# untitled.net
KiCad netlist of a schematic drawn in EAGLE
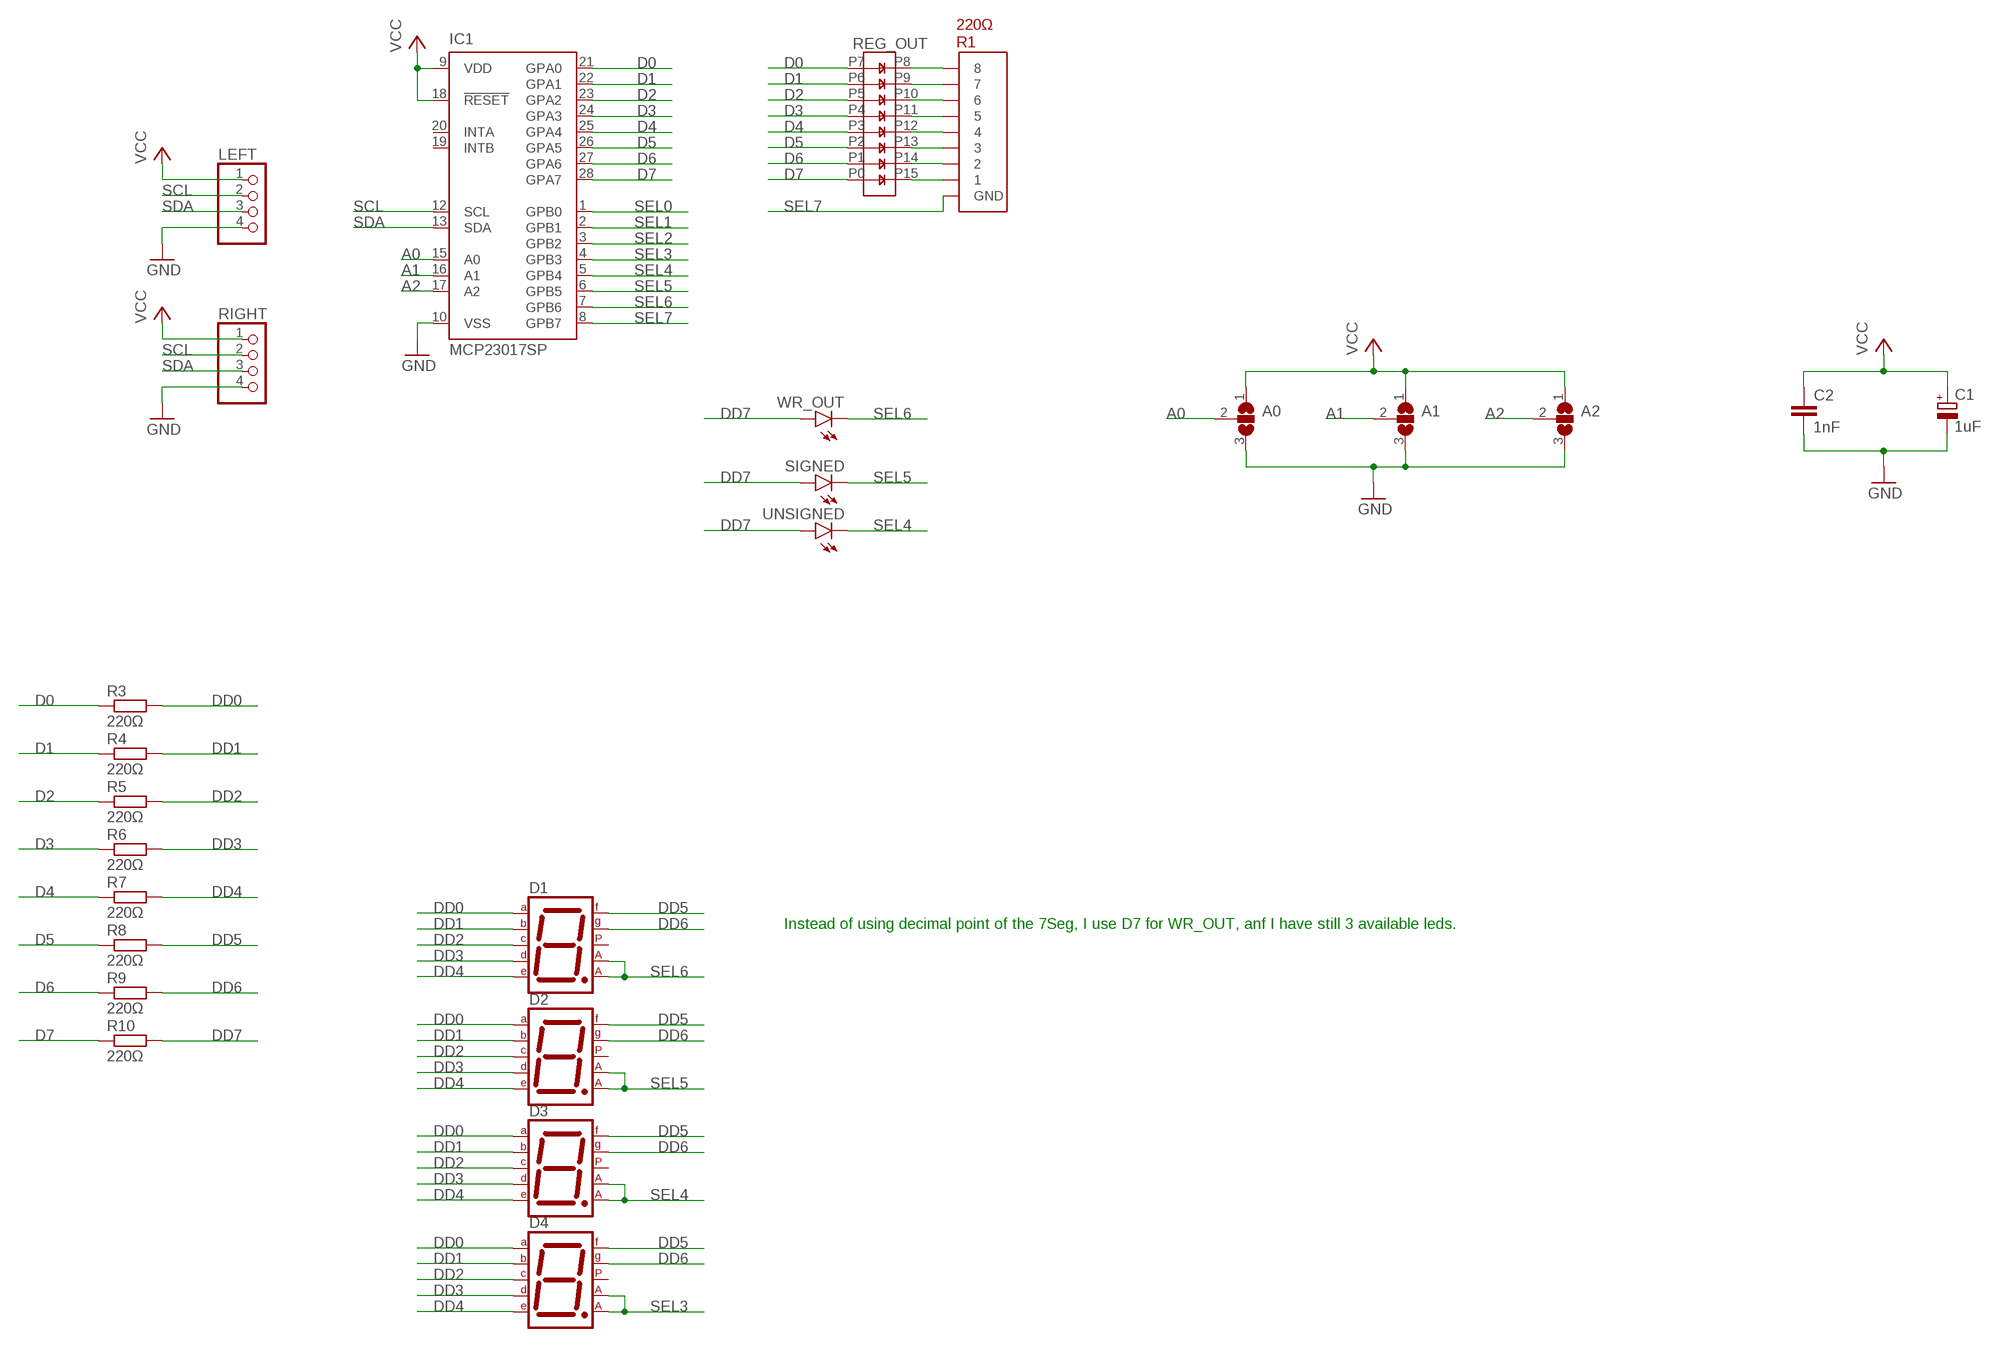
[diagram p0: schematic, sheet 1]

(export (version "E")
  (design (tool "Eeschema 10.0.6"))
  (components
    (comp (ref "A0")
      (value "SJ2W")
      (footprint "eagle-import:SJ_2")
      (libsource (lib "eagle-import") (part "SJ2W"))
    )
    (comp (ref "A1")
      (value "SJ2W")
      (footprint "eagle-import:SJ_2")
      (libsource (lib "eagle-import") (part "SJ2W"))
    )
    (comp (ref "A2")
      (value "SJ2W")
      (footprint "eagle-import:SJ_2")
      (libsource (lib "eagle-import") (part "SJ2W"))
    )
    (comp (ref "C1")
      (value "1uF")
      (footprint "eagle-import:E2,5-6")
      (libsource (lib "eagle-import") (part "CPOL-EUE2.5-6"))
    )
    (comp (ref "C2")
      (value "1nF")
      (footprint "eagle-import:C2.5-2")
      (libsource (lib "eagle-import") (part "C2.5/2"))
    )
    (comp (ref "D1")
      (value "7SEG-CA")
      (footprint "eagle-import:7SEG-13")
      (libsource (lib "eagle-import") (part "7SEG-CA"))
    )
    (comp (ref "D2")
      (value "7SEG-CA")
      (footprint "eagle-import:7SEG-13")
      (libsource (lib "eagle-import") (part "7SEG-CA"))
    )
    (comp (ref "D3")
      (value "7SEG-CA")
      (footprint "eagle-import:7SEG-13")
      (libsource (lib "eagle-import") (part "7SEG-CA"))
    )
    (comp (ref "D4")
      (value "7SEG-CA")
      (footprint "eagle-import:7SEG-13")
      (libsource (lib "eagle-import") (part "7SEG-CA"))
    )
    (comp (ref "IC1")
      (value "MCP23017SP")
      (footprint "eagle-import:DIL28-3")
      (fields (field (name "MF") "MICROCHIP") (field (name "MPN") "MCP23017-E/SP"))
      (libsource (lib "eagle-import") (part "MCP23017SP"))
    )
    (comp (ref "LEFT")
      (value "PINHD-1X4")
      (footprint "eagle-import:1X04")
      (libsource (lib "eagle-import") (part "PINHD-1X4"))
    )
    (comp (ref "R1")
      (value "220Ω")
      (footprint "eagle-import:R_ARRAY_8PIN")
      (libsource (lib "eagle-import") (part "R_ARRAY_8PIN"))
    )
    (comp (ref "R3")
      (value "220Ω")
      (footprint "eagle-import:0207_10")
      (libsource (lib "eagle-import") (part "R-EU_0207/10"))
    )
    (comp (ref "R4")
      (value "220Ω")
      (footprint "eagle-import:0207_10")
      (libsource (lib "eagle-import") (part "R-EU_0207/10"))
    )
    (comp (ref "R5")
      (value "220Ω")
      (footprint "eagle-import:0207_10")
      (libsource (lib "eagle-import") (part "R-EU_0207/10"))
    )
    (comp (ref "R6")
      (value "220Ω")
      (footprint "eagle-import:0207_10")
      (libsource (lib "eagle-import") (part "R-EU_0207/10"))
    )
    (comp (ref "R7")
      (value "220Ω")
      (footprint "eagle-import:0207_10")
      (libsource (lib "eagle-import") (part "R-EU_0207/10"))
    )
    (comp (ref "R8")
      (value "220Ω")
      (footprint "eagle-import:0207_10")
      (libsource (lib "eagle-import") (part "R-EU_0207/10"))
    )
    (comp (ref "R9")
      (value "220Ω")
      (footprint "eagle-import:0207_10")
      (libsource (lib "eagle-import") (part "R-EU_0207/10"))
    )
    (comp (ref "R10")
      (value "220Ω")
      (footprint "eagle-import:0207_10")
      (libsource (lib "eagle-import") (part "R-EU_0207/10"))
    )
    (comp (ref "REG_OUT")
      (value "LB8")
      (footprint "eagle-import:LB8")
      (libsource (lib "eagle-import") (part "LB8"))
    )
    (comp (ref "RIGHT")
      (value "PINHD-1X4")
      (footprint "eagle-import:1X04")
      (libsource (lib "eagle-import") (part "PINHD-1X4"))
    )
    (comp (ref "SIGNED")
      (value "LED3MM")
      (footprint "eagle-import:LED3MM")
      (libsource (lib "eagle-import") (part "LED3MM"))
    )
    (comp (ref "UNSIGNED")
      (value "LED3MM")
      (footprint "eagle-import:LED3MM")
      (libsource (lib "eagle-import") (part "LED3MM"))
    )
    (comp (ref "WR_OUT")
      (value "LED3MM")
      (footprint "eagle-import:LED3MM")
      (libsource (lib "eagle-import") (part "LED3MM"))
    )
  )
  (nets
    (net (code "1") (name "/A0") (class "Default")
      (node (ref "A0") (pin "2") (pinfunction "2_2") (pintype "passive"))
      (node (ref "IC1") (pin "15") (pinfunction "A0_15") (pintype "input"))
    )
    (net (code "2") (name "/A1") (class "Default")
      (node (ref "A1") (pin "2") (pinfunction "2_2") (pintype "passive"))
      (node (ref "IC1") (pin "16") (pinfunction "A1_16") (pintype "input"))
    )
    (net (code "3") (name "/A2") (class "Default")
      (node (ref "A2") (pin "2") (pinfunction "2_2") (pintype "passive"))
      (node (ref "IC1") (pin "17") (pinfunction "A2_17") (pintype "input"))
    )
    (net (code "4") (name "/D0") (class "Default")
      (node (ref "IC1") (pin "21") (pinfunction "GPA0_21") (pintype "bidirectional"))
      (node (ref "R3") (pin "1") (pinfunction "1_1") (pintype "passive"))
      (node (ref "REG_OUT") (pin "P7") (pinfunction "P7_P7") (pintype "bidirectional"))
    )
    (net (code "5") (name "/D1") (class "Default")
      (node (ref "IC1") (pin "22") (pinfunction "GPA1_22") (pintype "bidirectional"))
      (node (ref "R4") (pin "1") (pinfunction "1_1") (pintype "passive"))
      (node (ref "REG_OUT") (pin "P6") (pinfunction "P6_P6") (pintype "bidirectional"))
    )
    (net (code "6") (name "/D2") (class "Default")
      (node (ref "IC1") (pin "23") (pinfunction "GPA2_23") (pintype "bidirectional"))
      (node (ref "R5") (pin "1") (pinfunction "1_1") (pintype "passive"))
      (node (ref "REG_OUT") (pin "P5") (pinfunction "P5_P5") (pintype "bidirectional"))
    )
    (net (code "7") (name "/D3") (class "Default")
      (node (ref "IC1") (pin "24") (pinfunction "GPA3_24") (pintype "bidirectional"))
      (node (ref "R6") (pin "1") (pinfunction "1_1") (pintype "passive"))
      (node (ref "REG_OUT") (pin "P4") (pinfunction "P4_P4") (pintype "bidirectional"))
    )
    (net (code "8") (name "/D4") (class "Default")
      (node (ref "IC1") (pin "25") (pinfunction "GPA4_25") (pintype "bidirectional"))
      (node (ref "R7") (pin "1") (pinfunction "1_1") (pintype "passive"))
      (node (ref "REG_OUT") (pin "P3") (pinfunction "P3_P3") (pintype "bidirectional"))
    )
    (net (code "9") (name "/D5") (class "Default")
      (node (ref "IC1") (pin "26") (pinfunction "GPA5_26") (pintype "bidirectional"))
      (node (ref "R8") (pin "1") (pinfunction "1_1") (pintype "passive"))
      (node (ref "REG_OUT") (pin "P2") (pinfunction "P2_P2") (pintype "bidirectional"))
    )
    (net (code "10") (name "/D6") (class "Default")
      (node (ref "IC1") (pin "27") (pinfunction "GPA6_27") (pintype "bidirectional"))
      (node (ref "R9") (pin "1") (pinfunction "1_1") (pintype "passive"))
      (node (ref "REG_OUT") (pin "P1") (pinfunction "P1_P1") (pintype "bidirectional"))
    )
    (net (code "11") (name "/D7") (class "Default")
      (node (ref "IC1") (pin "28") (pinfunction "GPA7_28") (pintype "bidirectional"))
      (node (ref "R10") (pin "1") (pinfunction "1_1") (pintype "passive"))
      (node (ref "REG_OUT") (pin "P0") (pinfunction "P0_P0") (pintype "bidirectional"))
    )
    (net (code "12") (name "/DD0") (class "Default")
      (node (ref "D1") (pin "7") (pinfunction "A_7") (pintype "passive"))
      (node (ref "D2") (pin "7") (pinfunction "A_7") (pintype "passive"))
      (node (ref "D3") (pin "7") (pinfunction "A_7") (pintype "passive"))
      (node (ref "D4") (pin "7") (pinfunction "A_7") (pintype "passive"))
      (node (ref "R3") (pin "2") (pinfunction "2_2") (pintype "passive"))
    )
    (net (code "13") (name "/DD1") (class "Default")
      (node (ref "D1") (pin "6") (pinfunction "B_6") (pintype "passive"))
      (node (ref "D2") (pin "6") (pinfunction "B_6") (pintype "passive"))
      (node (ref "D3") (pin "6") (pinfunction "B_6") (pintype "passive"))
      (node (ref "D4") (pin "6") (pinfunction "B_6") (pintype "passive"))
      (node (ref "R4") (pin "2") (pinfunction "2_2") (pintype "passive"))
    )
    (net (code "14") (name "/DD2") (class "Default")
      (node (ref "D1") (pin "4") (pinfunction "C_4") (pintype "passive"))
      (node (ref "D2") (pin "4") (pinfunction "C_4") (pintype "passive"))
      (node (ref "D3") (pin "4") (pinfunction "C_4") (pintype "passive"))
      (node (ref "D4") (pin "4") (pinfunction "C_4") (pintype "passive"))
      (node (ref "R5") (pin "2") (pinfunction "2_2") (pintype "passive"))
    )
    (net (code "15") (name "/DD3") (class "Default")
      (node (ref "D1") (pin "2") (pinfunction "D_2") (pintype "passive"))
      (node (ref "D2") (pin "2") (pinfunction "D_2") (pintype "passive"))
      (node (ref "D3") (pin "2") (pinfunction "D_2") (pintype "passive"))
      (node (ref "D4") (pin "2") (pinfunction "D_2") (pintype "passive"))
      (node (ref "R6") (pin "2") (pinfunction "2_2") (pintype "passive"))
    )
    (net (code "16") (name "/DD4") (class "Default")
      (node (ref "D1") (pin "1") (pinfunction "E_1") (pintype "passive"))
      (node (ref "D2") (pin "1") (pinfunction "E_1") (pintype "passive"))
      (node (ref "D3") (pin "1") (pinfunction "E_1") (pintype "passive"))
      (node (ref "D4") (pin "1") (pinfunction "E_1") (pintype "passive"))
      (node (ref "R7") (pin "2") (pinfunction "2_2") (pintype "passive"))
    )
    (net (code "17") (name "/DD5") (class "Default")
      (node (ref "D1") (pin "9") (pinfunction "F_9") (pintype "passive"))
      (node (ref "D2") (pin "9") (pinfunction "F_9") (pintype "passive"))
      (node (ref "D3") (pin "9") (pinfunction "F_9") (pintype "passive"))
      (node (ref "D4") (pin "9") (pinfunction "F_9") (pintype "passive"))
      (node (ref "R8") (pin "2") (pinfunction "2_2") (pintype "passive"))
    )
    (net (code "18") (name "/DD6") (class "Default")
      (node (ref "D1") (pin "10") (pinfunction "G_10") (pintype "passive"))
      (node (ref "D2") (pin "10") (pinfunction "G_10") (pintype "passive"))
      (node (ref "D3") (pin "10") (pinfunction "G_10") (pintype "passive"))
      (node (ref "D4") (pin "10") (pinfunction "G_10") (pintype "passive"))
      (node (ref "R9") (pin "2") (pinfunction "2_2") (pintype "passive"))
    )
    (net (code "19") (name "/DD7") (class "Default")
      (node (ref "R10") (pin "2") (pinfunction "2_2") (pintype "passive"))
      (node (ref "SIGNED") (pin "A") (pinfunction "A_A") (pintype "passive"))
      (node (ref "UNSIGNED") (pin "A") (pinfunction "A_A") (pintype "passive"))
      (node (ref "WR_OUT") (pin "A") (pinfunction "A_A") (pintype "passive"))
    )
    (net (code "20") (name "/SCL") (class "Default")
      (node (ref "IC1") (pin "12") (pinfunction "SCL_12") (pintype "input"))
      (node (ref "LEFT") (pin "2") (pinfunction "2_2") (pintype "passive"))
      (node (ref "RIGHT") (pin "2") (pinfunction "2_2") (pintype "passive"))
    )
    (net (code "21") (name "/SDA") (class "Default")
      (node (ref "IC1") (pin "13") (pinfunction "SDA_13") (pintype "bidirectional"))
      (node (ref "LEFT") (pin "3") (pinfunction "3_3") (pintype "passive"))
      (node (ref "RIGHT") (pin "3") (pinfunction "3_3") (pintype "passive"))
    )
    (net (code "22") (name "/SEL0") (class "Default")
      (node (ref "IC1") (pin "1") (pinfunction "GPB0_1") (pintype "bidirectional"))
    )
    (net (code "23") (name "/SEL1") (class "Default")
      (node (ref "IC1") (pin "2") (pinfunction "GPB1_2") (pintype "bidirectional"))
    )
    (net (code "24") (name "/SEL2") (class "Default")
      (node (ref "IC1") (pin "3") (pinfunction "GPB2_3") (pintype "bidirectional"))
    )
    (net (code "25") (name "/SEL3") (class "Default")
      (node (ref "D4") (pin "3") (pinfunction "CA1_3") (pintype "passive"))
      (node (ref "D4") (pin "8") (pinfunction "CA2_8") (pintype "passive"))
      (node (ref "IC1") (pin "4") (pinfunction "GPB3_4") (pintype "bidirectional"))
    )
    (net (code "26") (name "/SEL4") (class "Default")
      (node (ref "D3") (pin "3") (pinfunction "CA1_3") (pintype "passive"))
      (node (ref "D3") (pin "8") (pinfunction "CA2_8") (pintype "passive"))
      (node (ref "IC1") (pin "5") (pinfunction "GPB4_5") (pintype "bidirectional"))
      (node (ref "UNSIGNED") (pin "K") (pinfunction "C_K") (pintype "passive"))
    )
    (net (code "27") (name "/SEL5") (class "Default")
      (node (ref "D2") (pin "3") (pinfunction "CA1_3") (pintype "passive"))
      (node (ref "D2") (pin "8") (pinfunction "CA2_8") (pintype "passive"))
      (node (ref "IC1") (pin "6") (pinfunction "GPB5_6") (pintype "bidirectional"))
      (node (ref "SIGNED") (pin "K") (pinfunction "C_K") (pintype "passive"))
    )
    (net (code "28") (name "/SEL6") (class "Default")
      (node (ref "D1") (pin "3") (pinfunction "CA1_3") (pintype "passive"))
      (node (ref "D1") (pin "8") (pinfunction "CA2_8") (pintype "passive"))
      (node (ref "IC1") (pin "7") (pinfunction "GPB6_7") (pintype "bidirectional"))
      (node (ref "WR_OUT") (pin "K") (pinfunction "C_K") (pintype "passive"))
    )
    (net (code "29") (name "/SEL7") (class "Default")
      (node (ref "IC1") (pin "8") (pinfunction "GPB7_8") (pintype "bidirectional"))
      (node (ref "R1") (pin "GND") (pinfunction "GND_GND") (pintype "bidirectional"))
    )
    (net (code "30") (name "GND") (class "Default")
      (node (ref "A0") (pin "3") (pinfunction "3_3") (pintype "passive"))
      (node (ref "A1") (pin "3") (pinfunction "3_3") (pintype "passive"))
      (node (ref "A2") (pin "3") (pinfunction "3_3") (pintype "passive"))
      (node (ref "C1") (pin "-") (pinfunction "-_-") (pintype "passive"))
      (node (ref "C2") (pin "2") (pinfunction "2_2") (pintype "passive"))
      (node (ref "IC1") (pin "10") (pinfunction "VSS_10") (pintype "power_in"))
      (node (ref "LEFT") (pin "4") (pinfunction "4_4") (pintype "passive"))
      (node (ref "RIGHT") (pin "4") (pinfunction "4_4") (pintype "passive"))
    )
    (net (code "31") (name "Net-(R1-Pad1)") (class "Default")
      (node (ref "R1") (pin "1") (pinfunction "1_1") (pintype "bidirectional"))
      (node (ref "REG_OUT") (pin "P15") (pinfunction "P15_P15") (pintype "bidirectional"))
    )
    (net (code "32") (name "Net-(R1-Pad2)") (class "Default")
      (node (ref "R1") (pin "2") (pinfunction "2_2") (pintype "bidirectional"))
      (node (ref "REG_OUT") (pin "P14") (pinfunction "P14_P14") (pintype "bidirectional"))
    )
    (net (code "33") (name "Net-(R1-Pad3)") (class "Default")
      (node (ref "R1") (pin "3") (pinfunction "3_3") (pintype "bidirectional"))
      (node (ref "REG_OUT") (pin "P13") (pinfunction "P13_P13") (pintype "bidirectional"))
    )
    (net (code "34") (name "Net-(R1-Pad4)") (class "Default")
      (node (ref "R1") (pin "4") (pinfunction "4_4") (pintype "bidirectional"))
      (node (ref "REG_OUT") (pin "P12") (pinfunction "P12_P12") (pintype "bidirectional"))
    )
    (net (code "35") (name "Net-(R1-Pad5)") (class "Default")
      (node (ref "R1") (pin "5") (pinfunction "5_5") (pintype "bidirectional"))
      (node (ref "REG_OUT") (pin "P11") (pinfunction "P11_P11") (pintype "bidirectional"))
    )
    (net (code "36") (name "Net-(R1-Pad6)") (class "Default")
      (node (ref "R1") (pin "6") (pinfunction "6_6") (pintype "bidirectional"))
      (node (ref "REG_OUT") (pin "P10") (pinfunction "P10_P10") (pintype "bidirectional"))
    )
    (net (code "37") (name "Net-(R1-Pad7)") (class "Default")
      (node (ref "R1") (pin "7") (pinfunction "7_7") (pintype "bidirectional"))
      (node (ref "REG_OUT") (pin "P9") (pinfunction "P9_P9") (pintype "bidirectional"))
    )
    (net (code "38") (name "Net-(R1-Pad8)") (class "Default")
      (node (ref "R1") (pin "8") (pinfunction "8_8") (pintype "bidirectional"))
      (node (ref "REG_OUT") (pin "P8") (pinfunction "P8_P8") (pintype "bidirectional"))
    )
    (net (code "39") (name "VCC") (class "Default")
      (node (ref "A0") (pin "1") (pinfunction "1_1") (pintype "passive"))
      (node (ref "A1") (pin "1") (pinfunction "1_1") (pintype "passive"))
      (node (ref "A2") (pin "1") (pinfunction "1_1") (pintype "passive"))
      (node (ref "C1") (pin "+") (pinfunction "+_+") (pintype "passive"))
      (node (ref "C2") (pin "1") (pinfunction "1_1") (pintype "passive"))
      (node (ref "IC1") (pin "18") (pinfunction "~{RESET}_18") (pintype "input"))
      (node (ref "IC1") (pin "9") (pinfunction "VDD_9") (pintype "power_in"))
      (node (ref "LEFT") (pin "1") (pinfunction "1_1") (pintype "passive"))
      (node (ref "RIGHT") (pin "1") (pinfunction "1_1") (pintype "passive"))
    )
    (net (code "40") (name "unconnected-(D1-DP-Pad5)") (class "Default")
      (node (ref "D1") (pin "5") (pinfunction "DP_5") (pintype "passive"))
    )
    (net (code "41") (name "unconnected-(D2-DP-Pad5)") (class "Default")
      (node (ref "D2") (pin "5") (pinfunction "DP_5") (pintype "passive"))
    )
    (net (code "42") (name "unconnected-(D3-DP-Pad5)") (class "Default")
      (node (ref "D3") (pin "5") (pinfunction "DP_5") (pintype "passive"))
    )
    (net (code "43") (name "unconnected-(D4-DP-Pad5)") (class "Default")
      (node (ref "D4") (pin "5") (pinfunction "DP_5") (pintype "passive"))
    )
    (net (code "44") (name "unconnected-(IC1-INTA-Pad20)") (class "Default")
      (node (ref "IC1") (pin "20") (pinfunction "INTA_20") (pintype "output"))
    )
    (net (code "45") (name "unconnected-(IC1-INTB-Pad19)") (class "Default")
      (node (ref "IC1") (pin "19") (pinfunction "INTB_19") (pintype "output"))
    )
  )
)
